# ProPrj_uHatv1.net
KiCad netlist of a schematic drawn in EasyEDA Pro
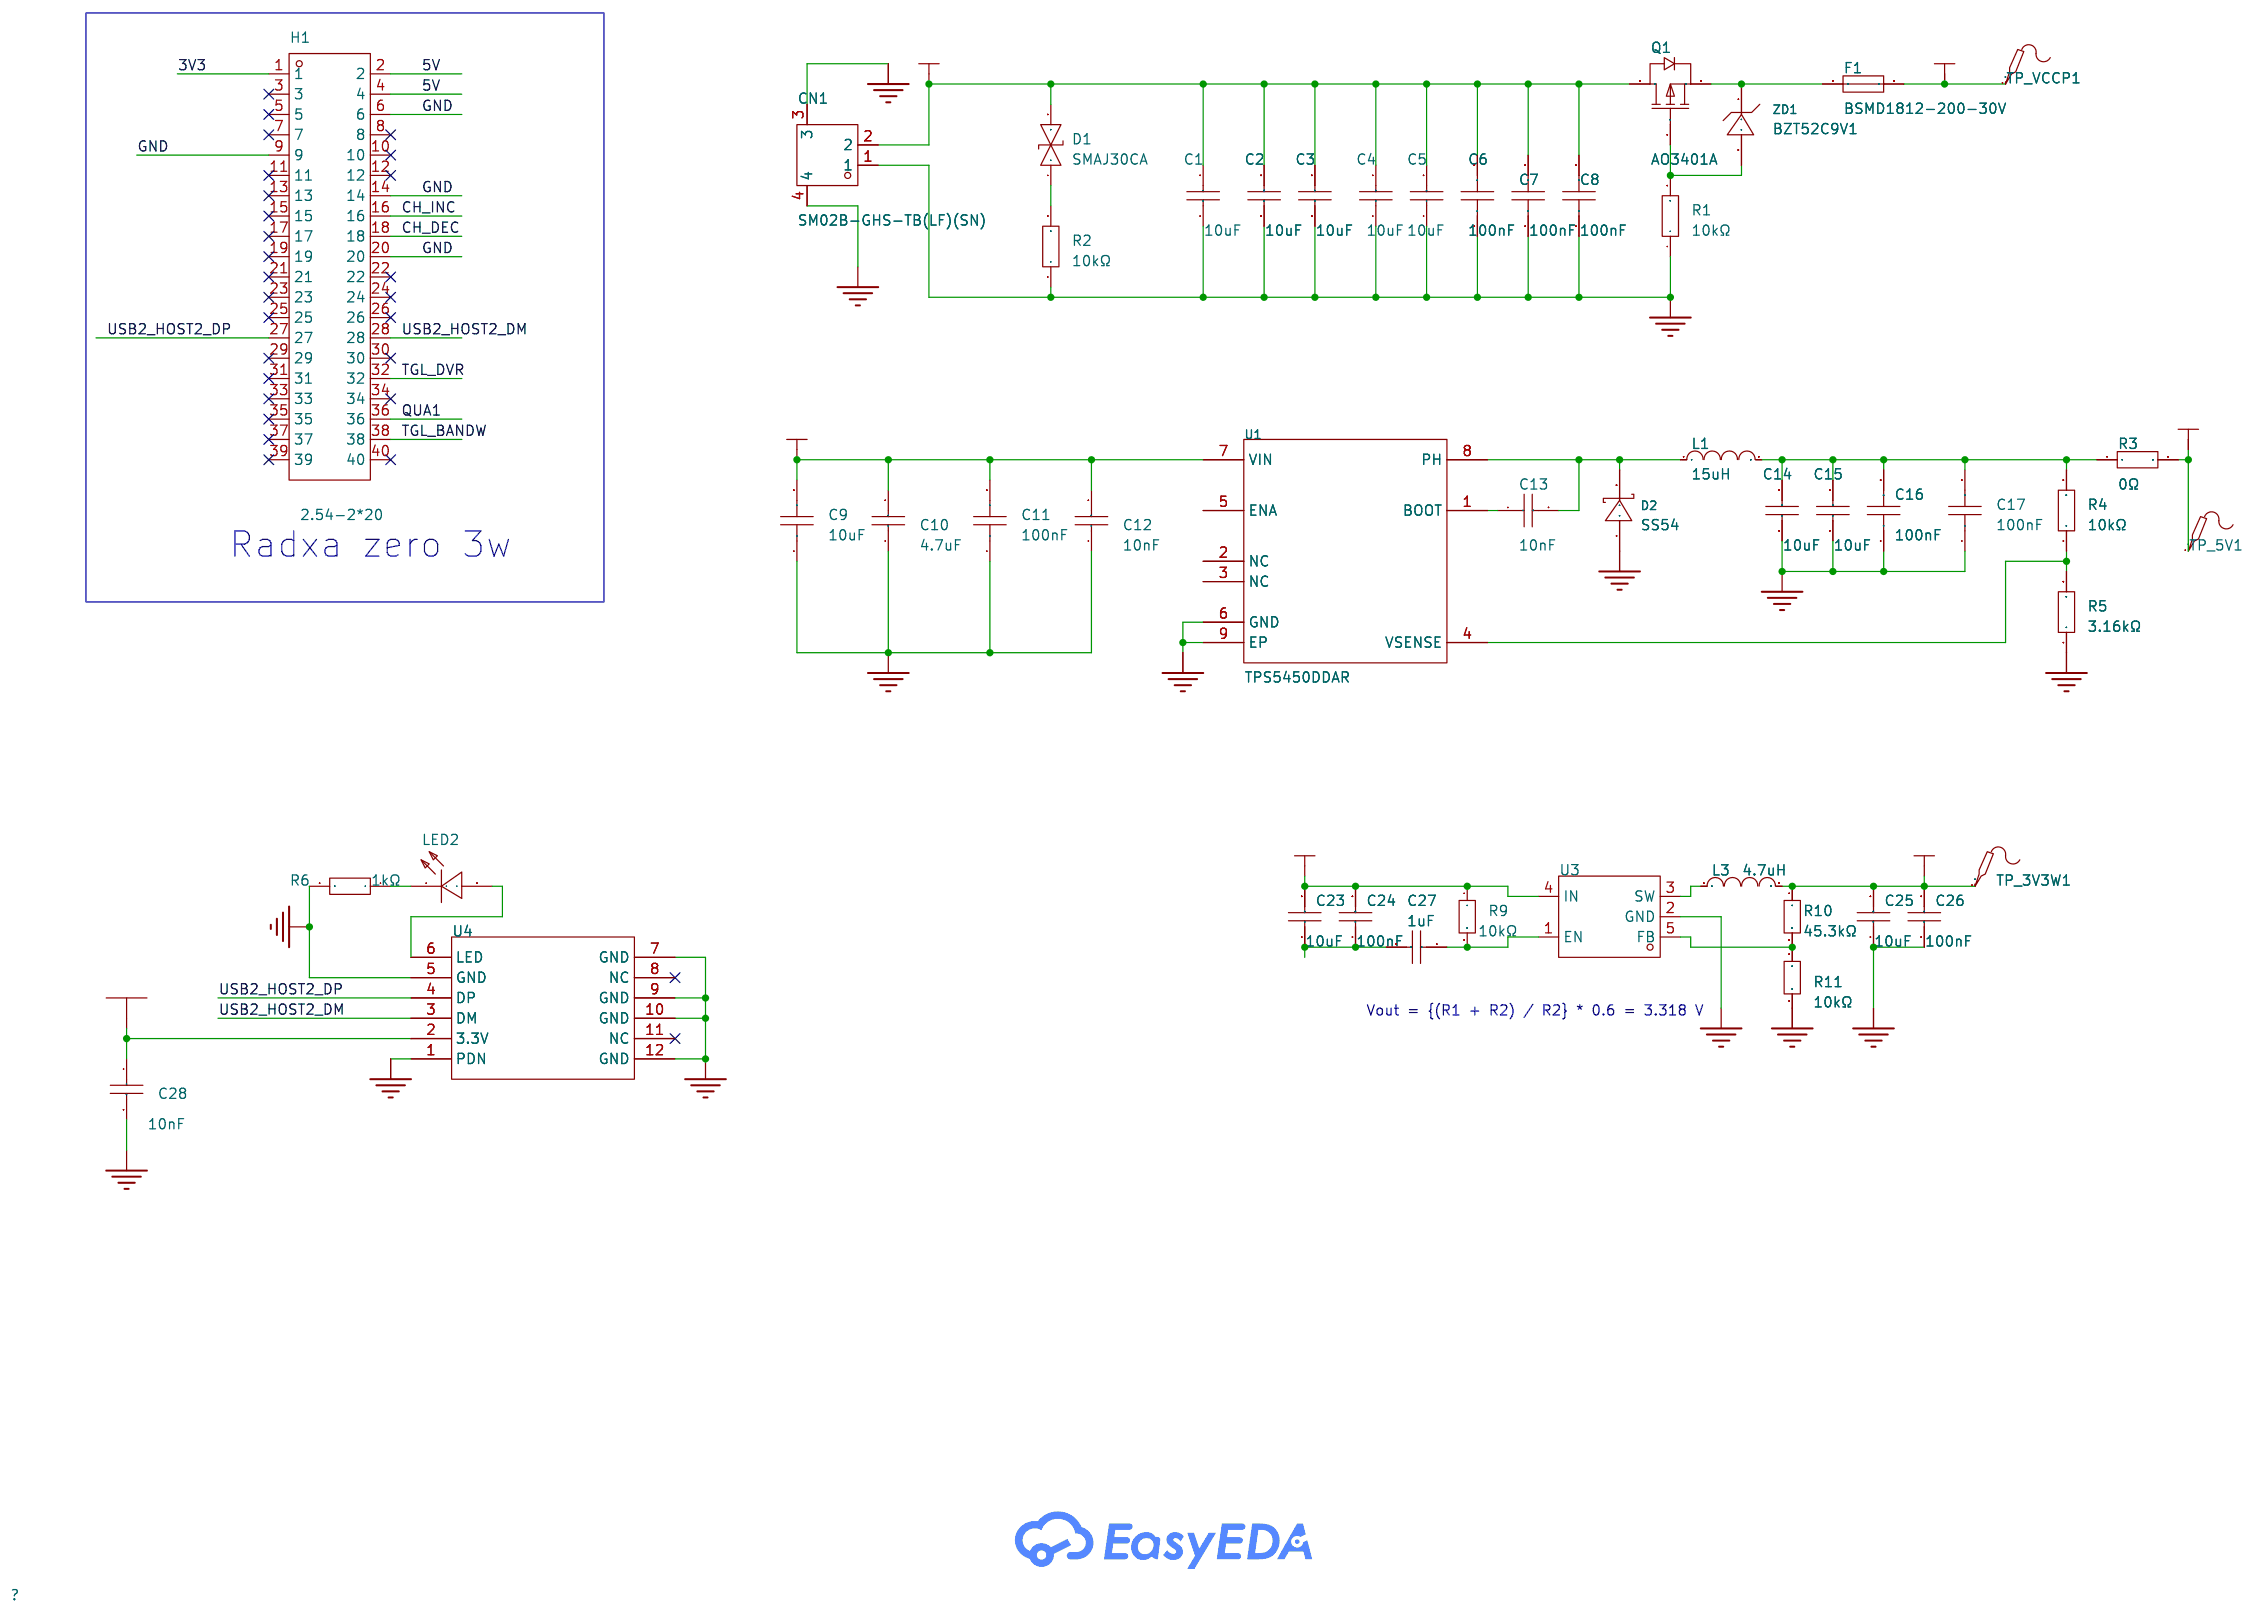
[diagram p0: schematic sheet]

(export (version "E")
  (design (tool "Eeschema 10.0.6"))
  (components
    (comp (ref "C1")
      (value "10uF")
      (footprint "easyedapro:C1206")
      (description "容值:10uF;精度:±10%;额定电压:50V;材质(温度系数):X5R;")
      (fields
        (field (name "Manufacturer Part") "CL31A106KBHNNNE")
        (field (name "Manufacturer") "SAMSUNG(三星)")
      )
      (libsource (lib "easyedapro") (part "CL31A106KBHNNNE"))
    )
    (comp (ref "C2")
      (value "10uF")
      (footprint "easyedapro:C1206")
      (description "容值:10uF;精度:±10%;额定电压:50V;材质(温度系数):X5R;")
      (fields
        (field (name "Manufacturer Part") "CL31A106KBHNNNE")
        (field (name "Manufacturer") "SAMSUNG(三星)")
      )
      (libsource (lib "easyedapro") (part "CL31A106KBHNNNE"))
    )
    (comp (ref "C3")
      (value "10uF")
      (footprint "easyedapro:C1206")
      (description "容值:10uF;精度:±10%;额定电压:50V;材质(温度系数):X5R;")
      (fields
        (field (name "Manufacturer Part") "CL31A106KBHNNNE")
        (field (name "Manufacturer") "SAMSUNG(三星)")
      )
      (libsource (lib "easyedapro") (part "CL31A106KBHNNNE"))
    )
    (comp (ref "C4")
      (value "10uF")
      (footprint "easyedapro:C1206")
      (description "容值:10uF;精度:±10%;额定电压:50V;材质(温度系数):X5R;")
      (fields
        (field (name "Manufacturer Part") "CL31A106KBHNNNE")
        (field (name "Manufacturer") "SAMSUNG(三星)")
      )
      (libsource (lib "easyedapro") (part "CL31A106KBHNNNE"))
    )
    (comp (ref "C5")
      (value "10uF")
      (footprint "easyedapro:C1206")
      (description "容值:10uF;精度:±10%;额定电压:50V;材质(温度系数):X5R;")
      (fields
        (field (name "Manufacturer Part") "CL31A106KBHNNNE")
        (field (name "Manufacturer") "SAMSUNG(三星)")
      )
      (libsource (lib "easyedapro") (part "CL31A106KBHNNNE"))
    )
    (comp (ref "C6")
      (value "100nF")
      (fields
        (field (name "Manufacturer Part") "CC0603KRX7R9BB104")
        (field (name "Manufacturer") "YAGEO(国巨)")
      )
      (libsource (lib "easyedapro") (part "CC0603KRX7R9BB104"))
    )
    (comp (ref "C7")
      (value "100nF")
      (fields
        (field (name "Manufacturer Part") "CC0603KRX7R9BB104")
        (field (name "Manufacturer") "YAGEO(国巨)")
      )
      (libsource (lib "easyedapro") (part "CC0603KRX7R9BB104"))
    )
    (comp (ref "C8")
      (value "100nF")
      (fields
        (field (name "Manufacturer Part") "CC0603KRX7R9BB104")
        (field (name "Manufacturer") "YAGEO(国巨)")
      )
      (libsource (lib "easyedapro") (part "CC0603KRX7R9BB104"))
    )
    (comp (ref "C9")
      (value "10uF")
      (footprint "easyedapro:C1206")
      (description "容值:10uF;精度:±10%;额定电压:50V;材质(温度系数):X7R;")
      (fields
        (field (name "Manufacturer Part") "CL31B106KBHNNNE")
        (field (name "Manufacturer") "SAMSUNG(三星)")
      )
      (libsource (lib "easyedapro") (part "CL31B106KBHNNNE"))
    )
    (comp (ref "C10")
      (value "4.7uF")
      (footprint "easyedapro:C1206")
      (description "容值:4.7uF;精度:±10%;额定电压:50V;材质(温度系数):X7R;")
      (fields
        (field (name "Manufacturer Part") "CL31B475KBHNNNE")
        (field (name "Manufacturer") "SAMSUNG(三星)")
      )
      (libsource (lib "easyedapro") (part "CL31B475KBHNNNE"))
    )
    (comp (ref "C11")
      (value "100nF")
      (fields
        (field (name "Manufacturer Part") "CC0603KRX7R9BB104")
        (field (name "Manufacturer") "YAGEO(国巨)")
      )
      (libsource (lib "easyedapro") (part "CC0603KRX7R9BB104"))
    )
    (comp (ref "C12")
      (value "10nF")
      (footprint "easyedapro:C0603")
      (description "容值:10nF;精度:±10%;额定电压:50V;材质(温度系数):X7R;")
      (fields
        (field (name "Manufacturer Part") "CC0603KRX7R9BB103")
        (field (name "Manufacturer") "YAGEO(国巨)")
      )
      (libsource (lib "easyedapro") (part "CC0603KRX7R9BB103"))
    )
    (comp (ref "C13")
      (value "10nF")
      (footprint "easyedapro:C0603")
      (description "容值:10nF;精度:±10%;额定电压:50V;材质(温度系数):X7R;")
      (fields
        (field (name "Manufacturer Part") "CC0603KRX7R9BB103")
        (field (name "Manufacturer") "YAGEO(国巨)")
      )
      (libsource (lib "easyedapro") (part "CC0603KRX7R9BB103"))
    )
    (comp (ref "C14")
      (value "10uF")
      (footprint "easyedapro:C1206")
      (description "容值:10uF;精度:±10%;额定电压:50V;材质(温度系数):X5R;")
      (fields
        (field (name "Manufacturer Part") "CL31A106KBHNNNE")
        (field (name "Manufacturer") "SAMSUNG(三星)")
      )
      (libsource (lib "easyedapro") (part "CL31A106KBHNNNE"))
    )
    (comp (ref "C15")
      (value "10uF")
      (footprint "easyedapro:C1206")
      (description "容值:10uF;精度:±10%;额定电压:50V;材质(温度系数):X5R;")
      (fields
        (field (name "Manufacturer Part") "CL31A106KBHNNNE")
        (field (name "Manufacturer") "SAMSUNG(三星)")
      )
      (libsource (lib "easyedapro") (part "CL31A106KBHNNNE"))
    )
    (comp (ref "C16")
      (value "100nF")
      (fields
        (field (name "Manufacturer Part") "CC0603KRX7R9BB104")
        (field (name "Manufacturer") "YAGEO(国巨)")
      )
      (libsource (lib "easyedapro") (part "CC0603KRX7R9BB104"))
    )
    (comp (ref "C17")
      (value "100nF")
      (fields
        (field (name "Manufacturer Part") "CC0603KRX7R9BB104")
        (field (name "Manufacturer") "YAGEO(国巨)")
      )
      (libsource (lib "easyedapro") (part "CC0603KRX7R9BB104"))
    )
    (comp (ref "C23")
      (value "10uF")
      (footprint "easyedapro:C0402")
      (description "容值:10uF;精度:±20%;额定电压:6.3V;温度系数:X5R;")
      (fields
        (field (name "Manufacturer Part") "CL05A106MQ5NUNC")
        (field (name "Manufacturer") "SAMSUNG(三星)")
      )
      (libsource (lib "easyedapro") (part "C 0402"))
    )
    (comp (ref "C24")
      (value "100nF")
      (footprint "easyedapro:C0402")
      (description "容值:10uF;精度:±20%;额定电压:6.3V;温度系数:X5R;")
      (fields
        (field (name "Manufacturer Part") "CL05B104KB54PNC")
        (field (name "Manufacturer") "SAMSUNG(三星)")
      )
      (libsource (lib "easyedapro") (part "C 0402"))
    )
    (comp (ref "C25")
      (value "10uF")
      (footprint "easyedapro:C0402")
      (description "容值:10uF;精度:±20%;额定电压:6.3V;温度系数:X5R;")
      (fields
        (field (name "Manufacturer Part") "CL05A106MQ5NUNC")
        (field (name "Manufacturer") "SAMSUNG(三星)")
      )
      (libsource (lib "easyedapro") (part "C 0402"))
    )
    (comp (ref "C26")
      (value "100nF")
      (footprint "easyedapro:C0402")
      (description "容值:10uF;精度:±20%;额定电压:6.3V;温度系数:X5R;")
      (fields
        (field (name "Manufacturer Part") "CL05B104KB54PNC")
        (field (name "Manufacturer") "SAMSUNG(三星)")
      )
      (libsource (lib "easyedapro") (part "C 0402"))
    )
    (comp (ref "C27")
      (value "1uF")
      (footprint "easyedapro:C0402")
      (description "容值:10uF;精度:±20%;额定电压:6.3V;温度系数:X5R;")
      (fields
        (field (name "Manufacturer Part") "CL05A105KA5NQNC")
        (field (name "Manufacturer") "SAMSUNG(三星)")
      )
      (libsource (lib "easyedapro") (part "C 0402"))
    )
    (comp (ref "C28")
      (value "10nF")
      (fields
        (field (name "Manufacturer Part") "CL05B103KB5NNNC")
        (field (name "Manufacturer") "SAMSUNG(三星)")
      )
      (libsource (lib "easyedapro") (part "10nF"))
    )
    (comp (ref "CN1")
      (value "SM02B-GHS-TB(LF)(SN)")
      (fields (field (name "Manufacturer") "JST"))
      (libsource (lib "easyedapro") (part "XT30PW-M"))
    )
    (comp (ref "D1")
      (value "SMAJ30CA")
      (footprint "easyedapro:SMA_L4.4-W2.6-LS5.0-BI")
      (description "极性:双向;反向截止电压(Vrwm):30V;击穿电压:33.3V;反向漏电流(Ir):1uA;峰值脉冲电流(Ipp)@10/1000μs:8.3A;最大钳位电压:48.4V;")
      (fields (field (name "Manufacturer") "MDD"))
      (libsource (lib "easyedapro") (part "SMAJ30CA-C110043"))
    )
    (comp (ref "D2")
      (value "SS54")
      (fields (field (name "Manufacturer") "宏迦橙"))
      (libsource (lib "easyedapro") (part "SS54_C22452"))
    )
    (comp (ref "F1")
      (value "BSMD1812-200-30V")
      (footprint "easyedapro:F1812")
      (description "最大电压:30V;最大电流:40A;保持电流:2A;跳闸电流:4A;")
      (fields (field (name "Manufacturer") "BHFUSE(佰宏)"))
      (libsource (lib "easyedapro") (part "BSMD1812-200-30V"))
    )
    (comp (ref "H1")
      (value "2.54-2*20")
      (footprint "easyedapro:HDR-SMD_40P-P2.54-V-F-R2-C20-S7.1-EH")
      (fields (field (name "Manufacturer") "ZHOURI(洲日)"))
      (libsource (lib "easyedapro") (part "FH-00148"))
    )
    (comp (ref "L1")
      (value "15uH")
      (footprint "easyedapro:IND-SMD_L7.3-W6.8")
      (description "精度:±20%;额定电流:3A;电感值:15uH;直流电阻(DCR):113mΩ;")
      (fields
        (field (name "Manufacturer Part") "MWSA0603S-150MT")
        (field (name "Manufacturer") "Sunlord(顺络)")
      )
      (libsource (lib "easyedapro") (part "MWSA0603S-150MT"))
    )
    (comp (ref "L3")
      (value "4.7uH")
      (fields
        (field (name "Manufacturer Part") "SLO252012F4R7MTT")
        (field (name "Manufacturer") "Sunltech(韩国顺磁)")
      )
      (libsource (lib "easyedapro") (part "IND-SMD L3.0-W3.0"))
    )
    (comp (ref "LED2")
      (value "NCD0603G1")
      (fields (field (name "Manufacturer") "国星光电"))
      (libsource (lib "easyedapro") (part "KT-0603R"))
    )
    (comp (ref "Q1")
      (value "AO3401A")
      (footprint "easyedapro:SOT-23_L2.9-W1.3-P1.90-LS2.4-BR")
      (description "类型:P沟道;漏源电压(Vdss):30V;连续漏极电流(Id):4A;功率(Pd):1.4W;导通电阻(RDS(on)@Vgs,Id):44mΩ@10V,4.3A;")
      (fields (field (name "Manufacturer") "AOS"))
      (libsource (lib "easyedapro") (part "AO3401A"))
    )
    (comp (ref "R1")
      (value "10kΩ")
      (footprint "easyedapro:R0603")
      (description "电阻类型:厚膜电阻;阻值:10kΩ;精度:±1%;功率:100mW;")
      (fields (field (name "Manufacturer Part") "RC0603FR-0710KL") (field (name "Manufacturer") "YAGEO(国巨)"))
      (libsource (lib "easyedapro") (part "RC0603FR-0710KL"))
    )
    (comp (ref "R2")
      (value "10kΩ")
      (footprint "easyedapro:R0603")
      (description "电阻类型:厚膜电阻;阻值:10kΩ;精度:±1%;功率:100mW;")
      (fields (field (name "Manufacturer Part") "RC0603FR-0710KL") (field (name "Manufacturer") "YAGEO(国巨)"))
      (libsource (lib "easyedapro") (part "RC0603FR-0710KL"))
    )
    (comp (ref "R3")
      (value "0Ω")
      (footprint "easyedapro:R0805")
      (description "电阻类型:厚膜电阻;阻值:0Ω;精度:-;功率:125mW;")
      (fields (field (name "Manufacturer Part") "RC0805FR-070RL") (field (name "Manufacturer") "YAGEO(国巨)"))
      (libsource (lib "easyedapro") (part "RC0805FR-070RL"))
    )
    (comp (ref "R4")
      (value "10kΩ")
      (footprint "easyedapro:R0603")
      (description "电阻类型:厚膜电阻;阻值:10kΩ;精度:±1%;功率:100mW;")
      (fields (field (name "Manufacturer Part") "RC0603FR-0710KL") (field (name "Manufacturer") "YAGEO(国巨)"))
      (libsource (lib "easyedapro") (part "RC0603FR-0710KL"))
    )
    (comp (ref "R5")
      (value "3.16kΩ")
      (footprint "easyedapro:R0603")
      (description "电阻类型:厚膜电阻;阻值:3.16kΩ;精度:±1%;功率:100mW;")
      (fields (field (name "Manufacturer Part") "RC0603FR-073K16L") (field (name "Manufacturer") "YAGEO(国巨)"))
      (libsource (lib "easyedapro") (part "RC0603FR-073K16L"))
    )
    (comp (ref "R6")
      (value "1kΩ")
      (footprint "easyedapro:R0402")
      (description "电阻类型:厚膜电阻;阻值:1kΩ;精度:±1%;功率:62.5mW;最大工作电压:50V;温度系数:±100ppm/°C;")
      (fields
        (field (name "Manufacturer Part") "0402WGF1001TCE")
        (field (name "Manufacturer") "UNI-ROYAL(厚声)")
      )
      (libsource (lib "easyedapro") (part "0402WGF1001TCE"))
    )
    (comp (ref "R9")
      (value "10kΩ")
      (footprint "easyedapro:R0402")
      (fields
        (field (name "Manufacturer Part") "0402WGF1002TCE")
        (field (name "Manufacturer") "UNI-ROYAL(厚声)")
      )
      (libsource (lib "easyedapro") (part "R0402"))
    )
    (comp (ref "R10")
      (value "45.3kΩ")
      (footprint "easyedapro:R0402")
      (fields
        (field (name "Manufacturer Part") "0402WGF1002TCE")
        (field (name "Manufacturer") "UNI-ROYAL(厚声)")
      )
      (libsource (lib "easyedapro") (part "R0402"))
    )
    (comp (ref "R11")
      (value "10kΩ")
      (footprint "easyedapro:R0402")
      (description "电阻类型:厚膜电阻;阻值:10kΩ;精度:±1%;功率:1/16W;温度系数:±100ppm/;最大工作电压:50V;工作温度范围:-55~+155;")
      (fields
        (field (name "Manufacturer Part") "0402WGF1002TCE")
        (field (name "Manufacturer") "UNI-ROYAL(厚声)")
      )
      (libsource (lib "easyedapro") (part "R0402"))
    )
    (comp (ref "TP_3V3W1")
      (value "~")
      (footprint "easyedapro:Test-Point-0.5mm")
      (description "Test Point 测试点")
      (libsource (lib "easyedapro") (part "Test-Point"))
    )
    (comp (ref "TP_5V1")
      (value "~")
      (footprint "easyedapro:Test-Point-0.5mm")
      (description "Test Point 测试点")
      (libsource (lib "easyedapro") (part "Test-Point"))
    )
    (comp (ref "TP_VCCP1")
      (value "~")
      (footprint "easyedapro:Test-Point-0.5mm")
      (description "Test Point 测试点")
      (libsource (lib "easyedapro") (part "Test-Point"))
    )
    (comp (ref "U1")
      (value "TPS5450DDAR")
      (footprint "easyedapro:SOP-8_L4.9-W3.9-P1.27-LS6.0-BL-EP")
      (fields (field (name "Manufacturer") "TI(德州仪器)"))
      (libsource (lib "easyedapro") (part "TPS5450DDAR"))
    )
    (comp (ref "U3")
      (value "RY3408")
      (fields (field (name "Manufacturer") "RYCHiP(蕊源)"))
      (libsource (lib "easyedapro") (part "RY3408"))
    )
    (comp (ref "U4") (value "~") (libsource (lib "easyedapro") (part "BL-R8812AF1")))
    (comp (ref "ZD1")
      (value "BZT52C9V1")
      (footprint "easyedapro:SOD-123_L2.8-W1.8-LS3.7-RD")
      (description "二极管配置:独立式;稳压值(标称值):9.1V;稳压值(范围):8.5V~9.6V;精度:-;功率:350mW;")
      (fields (field (name "Manufacturer") "CJ(江苏长电/长晶)"))
      (libsource (lib "easyedapro") (part "BZT52C9V1"))
    )
  )
  (nets
    (net (code "1") (name "/3V3") (class "Default")
      (node (ref "H1") (pin "1") (pinfunction "1_1") (pintype "unspecified"))
    )
    (net (code "2") (name "/CH_DEC") (class "Default")
      (node (ref "H1") (pin "18") (pinfunction "18_18") (pintype "unspecified"))
    )
    (net (code "3") (name "/CH_INC") (class "Default")
      (node (ref "H1") (pin "16") (pinfunction "16_16") (pintype "unspecified"))
    )
    (net (code "4") (name "/QUA1") (class "Default")
      (node (ref "H1") (pin "36") (pinfunction "36_36") (pintype "unspecified"))
    )
    (net (code "5") (name "/TGL_BANDW") (class "Default")
      (node (ref "H1") (pin "38") (pinfunction "38_38") (pintype "unspecified"))
    )
    (net (code "6") (name "/TGL_DVR") (class "Default")
      (node (ref "H1") (pin "32") (pinfunction "32_32") (pintype "unspecified"))
    )
    (net (code "7") (name "/USB2_HOST2_DM") (class "Default")
      (node (ref "H1") (pin "28") (pinfunction "28_28") (pintype "unspecified"))
      (node (ref "U4") (pin "3") (pinfunction "DM_3") (pintype "input"))
    )
    (net (code "8") (name "/USB2_HOST2_DP") (class "Default")
      (node (ref "H1") (pin "27") (pinfunction "27_27") (pintype "unspecified"))
      (node (ref "U4") (pin "4") (pinfunction "DP_4") (pintype "input"))
    )
    (net (code "9") (name "3V3_WF") (class "Default")
      (node (ref "C25") (pin "2") (pinfunction "2_2") (pintype "input"))
      (node (ref "C26") (pin "2") (pinfunction "2_2") (pintype "input"))
      (node (ref "C28") (pin "1") (pinfunction "1_1") (pintype "input"))
      (node (ref "L3") (pin "2") (pinfunction "2_2") (pintype "input"))
      (node (ref "R10") (pin "1") (pinfunction "1_1") (pintype "input"))
      (node (ref "TP_3V3W1") (pin "1") (pinfunction "1_1") (pintype "input"))
      (node (ref "U4") (pin "2") (pinfunction "3.3V_2") (pintype "input"))
    )
    (net (code "10") (name "5V") (class "Default")
      (node (ref "C23") (pin "2") (pinfunction "2_2") (pintype "input"))
      (node (ref "C24") (pin "2") (pinfunction "2_2") (pintype "input"))
      (node (ref "H1") (pin "2") (pinfunction "2_2") (pintype "unspecified"))
      (node (ref "H1") (pin "4") (pinfunction "4_4") (pintype "unspecified"))
      (node (ref "R3") (pin "2") (pinfunction "2_2") (pintype "input"))
      (node (ref "R9") (pin "1") (pinfunction "1_1") (pintype "input"))
      (node (ref "TP_5V1") (pin "1") (pinfunction "1_1") (pintype "input"))
      (node (ref "U3") (pin "4") (pinfunction "IN_4") (pintype "input"))
    )
    (net (code "11") (name "GND") (class "Default")
      (node (ref "C1") (pin "1") (pinfunction "1_1") (pintype "input"))
      (node (ref "C10") (pin "1") (pinfunction "1_1") (pintype "input"))
      (node (ref "C11") (pin "1") (pinfunction "1_1") (pintype "input"))
      (node (ref "C12") (pin "1") (pinfunction "1_1") (pintype "input"))
      (node (ref "C14") (pin "1") (pinfunction "1_1") (pintype "input"))
      (node (ref "C15") (pin "1") (pinfunction "1_1") (pintype "input"))
      (node (ref "C16") (pin "1") (pinfunction "1_1") (pintype "input"))
      (node (ref "C17") (pin "1") (pinfunction "1_1") (pintype "input"))
      (node (ref "C2") (pin "1") (pinfunction "1_1") (pintype "input"))
      (node (ref "C25") (pin "1") (pinfunction "1_1") (pintype "input"))
      (node (ref "C26") (pin "1") (pinfunction "1_1") (pintype "input"))
      (node (ref "C28") (pin "2") (pinfunction "2_2") (pintype "input"))
      (node (ref "C3") (pin "1") (pinfunction "1_1") (pintype "input"))
      (node (ref "C4") (pin "1") (pinfunction "1_1") (pintype "input"))
      (node (ref "C5") (pin "1") (pinfunction "1_1") (pintype "input"))
      (node (ref "C6") (pin "1") (pinfunction "1_1") (pintype "input"))
      (node (ref "C7") (pin "1") (pinfunction "1_1") (pintype "input"))
      (node (ref "C8") (pin "1") (pinfunction "1_1") (pintype "input"))
      (node (ref "C9") (pin "1") (pinfunction "1_1") (pintype "input"))
      (node (ref "CN1") (pin "1") (pinfunction "1_1") (pintype "input"))
      (node (ref "CN1") (pin "3") (pinfunction "3_3") (pintype "input"))
      (node (ref "CN1") (pin "4") (pinfunction "4_4") (pintype "input"))
      (node (ref "D2") (pin "1") (pinfunction "A_1") (pintype "input"))
      (node (ref "H1") (pin "14") (pinfunction "14_14") (pintype "unspecified"))
      (node (ref "H1") (pin "20") (pinfunction "20_20") (pintype "unspecified"))
      (node (ref "H1") (pin "6") (pinfunction "6_6") (pintype "unspecified"))
      (node (ref "H1") (pin "9") (pinfunction "9_9") (pintype "unspecified"))
      (node (ref "R1") (pin "1") (pinfunction "1_1") (pintype "input"))
      (node (ref "R11") (pin "1") (pinfunction "1_1") (pintype "input"))
      (node (ref "R2") (pin "1") (pinfunction "1_1") (pintype "input"))
      (node (ref "R5") (pin "1") (pinfunction "1_1") (pintype "input"))
      (node (ref "R6") (pin "2") (pinfunction "2_2") (pintype "input"))
      (node (ref "U1") (pin "6") (pinfunction "GND_6") (pintype "input"))
      (node (ref "U1") (pin "9") (pinfunction "EP_9") (pintype "input"))
      (node (ref "U3") (pin "2") (pinfunction "GND_2") (pintype "input"))
      (node (ref "U4") (pin "1") (pinfunction "PDN_1") (pintype "input"))
      (node (ref "U4") (pin "10") (pinfunction "GND_10") (pintype "input"))
      (node (ref "U4") (pin "12") (pinfunction "GND_12") (pintype "input"))
      (node (ref "U4") (pin "5") (pinfunction "GND_5") (pintype "input"))
      (node (ref "U4") (pin "7") (pinfunction "GND_7") (pintype "input"))
      (node (ref "U4") (pin "9") (pinfunction "GND_9") (pintype "input"))
    )
    (net (code "12") (name "Net-(C14-Pad2)") (class "Default")
      (node (ref "C14") (pin "2") (pinfunction "2_2") (pintype "input"))
      (node (ref "C15") (pin "2") (pinfunction "2_2") (pintype "input"))
      (node (ref "C16") (pin "2") (pinfunction "2_2") (pintype "input"))
      (node (ref "C17") (pin "2") (pinfunction "2_2") (pintype "input"))
      (node (ref "L1") (pin "2") (pinfunction "2_2") (pintype "input"))
      (node (ref "R3") (pin "1") (pinfunction "1_1") (pintype "input"))
      (node (ref "R4") (pin "2") (pinfunction "2_2") (pintype "input"))
    )
    (net (code "13") (name "Net-(C23-Pad1)") (class "Default")
      (node (ref "C23") (pin "1") (pinfunction "1_1") (pintype "input"))
      (node (ref "C24") (pin "1") (pinfunction "1_1") (pintype "input"))
      (node (ref "C27") (pin "2") (pinfunction "2_2") (pintype "input"))
    )
    (net (code "14") (name "Net-(D1-Pad1)") (class "Default")
      (node (ref "D1") (pin "1") (pinfunction "1_1") (pintype "input"))
      (node (ref "R2") (pin "2") (pinfunction "2_2") (pintype "input"))
    )
    (net (code "15") (name "Net-(D2-K)") (class "Default")
      (node (ref "C13") (pin "2") (pinfunction "2_2") (pintype "input"))
      (node (ref "D2") (pin "2") (pinfunction "K_2") (pintype "input"))
      (node (ref "L1") (pin "1") (pinfunction "1_1") (pintype "input"))
      (node (ref "U1") (pin "8") (pinfunction "PH_8") (pintype "output"))
    )
    (net (code "16") (name "Net-(LED2-A)") (class "Default")
      (node (ref "LED2") (pin "2") (pinfunction "A_2") (pintype "input"))
      (node (ref "U4") (pin "6") (pinfunction "LED_6") (pintype "input"))
    )
    (net (code "17") (name "Net-(LED2-K)") (class "Default")
      (node (ref "LED2") (pin "1") (pinfunction "K_1") (pintype "input"))
      (node (ref "R6") (pin "1") (pinfunction "1_1") (pintype "input"))
    )
    (net (code "18") (name "Net-(Q1-G)") (class "Default")
      (node (ref "Q1") (pin "1") (pinfunction "G_1") (pintype "unspecified"))
      (node (ref "R1") (pin "2") (pinfunction "2_2") (pintype "input"))
      (node (ref "ZD1") (pin "2") (pinfunction "A_2") (pintype "input"))
    )
    (net (code "19") (name "Net-(Q1-S)") (class "Default")
      (node (ref "F1") (pin "1") (pinfunction "1_1") (pintype "input"))
      (node (ref "Q1") (pin "2") (pinfunction "S_2") (pintype "unspecified"))
      (node (ref "ZD1") (pin "1") (pinfunction "K_1") (pintype "input"))
    )
    (net (code "20") (name "Net-(U1-BOOT)") (class "Default")
      (node (ref "C13") (pin "1") (pinfunction "1_1") (pintype "input"))
      (node (ref "U1") (pin "1") (pinfunction "BOOT_1") (pintype "input"))
    )
    (net (code "21") (name "Net-(U1-VSENSE)") (class "Default")
      (node (ref "R4") (pin "1") (pinfunction "1_1") (pintype "input"))
      (node (ref "R5") (pin "2") (pinfunction "2_2") (pintype "input"))
      (node (ref "U1") (pin "4") (pinfunction "VSENSE_4") (pintype "output"))
    )
    (net (code "22") (name "Net-(U3-EN)") (class "Default")
      (node (ref "C27") (pin "1") (pinfunction "1_1") (pintype "input"))
      (node (ref "R9") (pin "2") (pinfunction "2_2") (pintype "input"))
      (node (ref "U3") (pin "1") (pinfunction "EN_1") (pintype "input"))
    )
    (net (code "23") (name "Net-(U3-FB)") (class "Default")
      (node (ref "R10") (pin "2") (pinfunction "2_2") (pintype "input"))
      (node (ref "R11") (pin "2") (pinfunction "2_2") (pintype "input"))
      (node (ref "U3") (pin "5") (pinfunction "FB_5") (pintype "input"))
    )
    (net (code "24") (name "Net-(U3-SW)") (class "Default")
      (node (ref "L3") (pin "1") (pinfunction "1_1") (pintype "input"))
      (node (ref "U3") (pin "3") (pinfunction "SW_3") (pintype "input"))
    )
    (net (code "25") (name "VCC_IN") (class "Default")
      (node (ref "C1") (pin "2") (pinfunction "2_2") (pintype "input"))
      (node (ref "C2") (pin "2") (pinfunction "2_2") (pintype "input"))
      (node (ref "C3") (pin "2") (pinfunction "2_2") (pintype "input"))
      (node (ref "C4") (pin "2") (pinfunction "2_2") (pintype "input"))
      (node (ref "C5") (pin "2") (pinfunction "2_2") (pintype "input"))
      (node (ref "C6") (pin "2") (pinfunction "2_2") (pintype "input"))
      (node (ref "C7") (pin "2") (pinfunction "2_2") (pintype "input"))
      (node (ref "C8") (pin "2") (pinfunction "2_2") (pintype "input"))
      (node (ref "CN1") (pin "2") (pinfunction "2_2") (pintype "input"))
      (node (ref "D1") (pin "2") (pinfunction "2_2") (pintype "input"))
      (node (ref "Q1") (pin "3") (pinfunction "D_3") (pintype "unspecified"))
    )
    (net (code "26") (name "VCC_P") (class "Default")
      (node (ref "C10") (pin "2") (pinfunction "2_2") (pintype "input"))
      (node (ref "C11") (pin "2") (pinfunction "2_2") (pintype "input"))
      (node (ref "C12") (pin "2") (pinfunction "2_2") (pintype "input"))
      (node (ref "C9") (pin "2") (pinfunction "2_2") (pintype "input"))
      (node (ref "F1") (pin "2") (pinfunction "2_2") (pintype "input"))
      (node (ref "TP_VCCP1") (pin "1") (pinfunction "1_1") (pintype "input"))
      (node (ref "U1") (pin "7") (pinfunction "VIN_7") (pintype "input"))
    )
    (net (code "27") (name "unconnected-(H1-Pad3)") (class "Default")
      (node (ref "H1") (pin "3") (pinfunction "3_3") (pintype "unspecified+no_connect"))
    )
    (net (code "28") (name "unconnected-(H1-Pad5)") (class "Default")
      (node (ref "H1") (pin "5") (pinfunction "5_5") (pintype "unspecified+no_connect"))
    )
    (net (code "29") (name "unconnected-(H1-Pad7)") (class "Default")
      (node (ref "H1") (pin "7") (pinfunction "7_7") (pintype "unspecified+no_connect"))
    )
    (net (code "30") (name "unconnected-(H1-Pad8)") (class "Default")
      (node (ref "H1") (pin "8") (pinfunction "8_8") (pintype "unspecified+no_connect"))
    )
    (net (code "31") (name "unconnected-(H1-Pad10)") (class "Default")
      (node (ref "H1") (pin "10") (pinfunction "10_10") (pintype "unspecified+no_connect"))
    )
    (net (code "32") (name "unconnected-(H1-Pad11)") (class "Default")
      (node (ref "H1") (pin "11") (pinfunction "11_11") (pintype "unspecified+no_connect"))
    )
    (net (code "33") (name "unconnected-(H1-Pad12)") (class "Default")
      (node (ref "H1") (pin "12") (pinfunction "12_12") (pintype "unspecified+no_connect"))
    )
    (net (code "34") (name "unconnected-(H1-Pad13)") (class "Default")
      (node (ref "H1") (pin "13") (pinfunction "13_13") (pintype "unspecified+no_connect"))
    )
    (net (code "35") (name "unconnected-(H1-Pad15)") (class "Default")
      (node (ref "H1") (pin "15") (pinfunction "15_15") (pintype "unspecified+no_connect"))
    )
    (net (code "36") (name "unconnected-(H1-Pad17)") (class "Default")
      (node (ref "H1") (pin "17") (pinfunction "17_17") (pintype "unspecified+no_connect"))
    )
    (net (code "37") (name "unconnected-(H1-Pad19)") (class "Default")
      (node (ref "H1") (pin "19") (pinfunction "19_19") (pintype "unspecified+no_connect"))
    )
    (net (code "38") (name "unconnected-(H1-Pad21)") (class "Default")
      (node (ref "H1") (pin "21") (pinfunction "21_21") (pintype "unspecified+no_connect"))
    )
    (net (code "39") (name "unconnected-(H1-Pad22)") (class "Default")
      (node (ref "H1") (pin "22") (pinfunction "22_22") (pintype "unspecified+no_connect"))
    )
    (net (code "40") (name "unconnected-(H1-Pad23)") (class "Default")
      (node (ref "H1") (pin "23") (pinfunction "23_23") (pintype "unspecified+no_connect"))
    )
    (net (code "41") (name "unconnected-(H1-Pad24)") (class "Default")
      (node (ref "H1") (pin "24") (pinfunction "24_24") (pintype "unspecified+no_connect"))
    )
    (net (code "42") (name "unconnected-(H1-Pad25)") (class "Default")
      (node (ref "H1") (pin "25") (pinfunction "25_25") (pintype "unspecified+no_connect"))
    )
    (net (code "43") (name "unconnected-(H1-Pad26)") (class "Default")
      (node (ref "H1") (pin "26") (pinfunction "26_26") (pintype "unspecified+no_connect"))
    )
    (net (code "44") (name "unconnected-(H1-Pad29)") (class "Default")
      (node (ref "H1") (pin "29") (pinfunction "29_29") (pintype "unspecified+no_connect"))
    )
    (net (code "45") (name "unconnected-(H1-Pad30)") (class "Default")
      (node (ref "H1") (pin "30") (pinfunction "30_30") (pintype "unspecified+no_connect"))
    )
    (net (code "46") (name "unconnected-(H1-Pad31)") (class "Default")
      (node (ref "H1") (pin "31") (pinfunction "31_31") (pintype "unspecified+no_connect"))
    )
    (net (code "47") (name "unconnected-(H1-Pad33)") (class "Default")
      (node (ref "H1") (pin "33") (pinfunction "33_33") (pintype "unspecified+no_connect"))
    )
    (net (code "48") (name "unconnected-(H1-Pad34)") (class "Default")
      (node (ref "H1") (pin "34") (pinfunction "34_34") (pintype "unspecified+no_connect"))
    )
    (net (code "49") (name "unconnected-(H1-Pad35)") (class "Default")
      (node (ref "H1") (pin "35") (pinfunction "35_35") (pintype "unspecified+no_connect"))
    )
    (net (code "50") (name "unconnected-(H1-Pad37)") (class "Default")
      (node (ref "H1") (pin "37") (pinfunction "37_37") (pintype "unspecified+no_connect"))
    )
    (net (code "51") (name "unconnected-(H1-Pad39)") (class "Default")
      (node (ref "H1") (pin "39") (pinfunction "39_39") (pintype "unspecified+no_connect"))
    )
    (net (code "52") (name "unconnected-(H1-Pad40)") (class "Default")
      (node (ref "H1") (pin "40") (pinfunction "40_40") (pintype "unspecified+no_connect"))
    )
    (net (code "53") (name "unconnected-(U1-ENA-Pad5)") (class "Default")
      (node (ref "U1") (pin "5") (pinfunction "ENA_5") (pintype "input"))
    )
    (net (code "54") (name "unconnected-(U1-NC-Pad2)") (class "Default")
      (node (ref "U1") (pin "2") (pinfunction "NC_2") (pintype "input"))
    )
    (net (code "55") (name "unconnected-(U1-NC-Pad3)") (class "Default")
      (node (ref "U1") (pin "3") (pinfunction "NC_3") (pintype "input"))
    )
    (net (code "56") (name "unconnected-(U4-NC-Pad8)") (class "Default")
      (node (ref "U4") (pin "8") (pinfunction "NC_8") (pintype "input+no_connect"))
    )
    (net (code "57") (name "unconnected-(U4-NC-Pad11)") (class "Default")
      (node (ref "U4") (pin "11") (pinfunction "NC_11") (pintype "input+no_connect"))
    )
  )
)
